# untitled.net
KiCad netlist of a schematic drawn in EAGLE
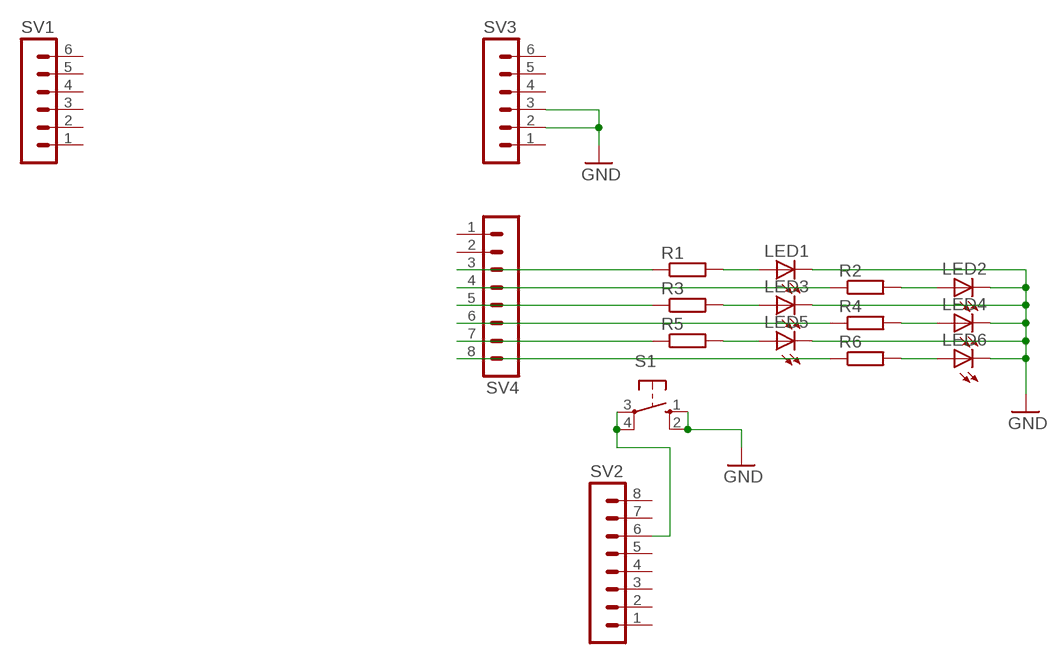
[diagram p0: schematic, sheet 1]

(export (version "E")
  (design (tool "Eeschema 10.0.6"))
  (components
    (comp (ref "LED1")
      (value "LED3MM")
      (footprint "eagle-import:LED3MM")
      (libsource (lib "eagle-import") (part "LED3MM"))
    )
    (comp (ref "LED2")
      (value "LED3MM")
      (footprint "eagle-import:LED3MM")
      (libsource (lib "eagle-import") (part "LED3MM"))
    )
    (comp (ref "LED3")
      (value "LED3MM")
      (footprint "eagle-import:LED3MM")
      (libsource (lib "eagle-import") (part "LED3MM"))
    )
    (comp (ref "LED4")
      (value "LED3MM")
      (footprint "eagle-import:LED3MM")
      (libsource (lib "eagle-import") (part "LED3MM"))
    )
    (comp (ref "LED5")
      (value "LED3MM")
      (footprint "eagle-import:LED3MM")
      (libsource (lib "eagle-import") (part "LED3MM"))
    )
    (comp (ref "LED6")
      (value "LED3MM")
      (footprint "eagle-import:LED3MM")
      (libsource (lib "eagle-import") (part "LED3MM"))
    )
    (comp (ref "R1")
      (value "R-EU_0207/10")
      (footprint "eagle-import:0207_10")
      (libsource (lib "eagle-import") (part "R-EU_0207/10"))
    )
    (comp (ref "R2")
      (value "R-EU_0207/10")
      (footprint "eagle-import:0207_10")
      (libsource (lib "eagle-import") (part "R-EU_0207/10"))
    )
    (comp (ref "R3")
      (value "R-EU_0207/10")
      (footprint "eagle-import:0207_10")
      (libsource (lib "eagle-import") (part "R-EU_0207/10"))
    )
    (comp (ref "R4")
      (value "R-EU_0207/10")
      (footprint "eagle-import:0207_10")
      (libsource (lib "eagle-import") (part "R-EU_0207/10"))
    )
    (comp (ref "R5")
      (value "R-EU_0207/10")
      (footprint "eagle-import:0207_10")
      (libsource (lib "eagle-import") (part "R-EU_0207/10"))
    )
    (comp (ref "R6")
      (value "R-EU_0207/10")
      (footprint "eagle-import:0207_10")
      (libsource (lib "eagle-import") (part "R-EU_0207/10"))
    )
    (comp (ref "S1")
      (value "40-XX")
      (footprint "eagle-import:B3F-40XX")
      (fields (field (name "MF") "OMRON COMPONENTS USA") (field (name "MPN") "B3F-4000"))
      (libsource (lib "eagle-import") (part "40-XX"))
    )
    (comp (ref "SV1")
      (value "MA06-1")
      (footprint "eagle-import:MA06-1")
      (libsource (lib "eagle-import") (part "MA06-1"))
    )
    (comp (ref "SV2")
      (value "MA08-1")
      (footprint "eagle-import:MA08-1")
      (libsource (lib "eagle-import") (part "MA08-1"))
    )
    (comp (ref "SV3")
      (value "MA06-1")
      (footprint "eagle-import:MA06-1")
      (libsource (lib "eagle-import") (part "MA06-1"))
    )
    (comp (ref "SV4")
      (value "MA08-1")
      (footprint "eagle-import:MA08-1")
      (libsource (lib "eagle-import") (part "MA08-1"))
    )
  )
  (nets
    (net (code "1") (name "GND") (class "Default")
      (node (ref "LED1") (pin "K") (pinfunction "C_K") (pintype "passive"))
      (node (ref "LED2") (pin "K") (pinfunction "C_K") (pintype "passive"))
      (node (ref "LED3") (pin "K") (pinfunction "C_K") (pintype "passive"))
      (node (ref "LED4") (pin "K") (pinfunction "C_K") (pintype "passive"))
      (node (ref "LED5") (pin "K") (pinfunction "C_K") (pintype "passive"))
      (node (ref "LED6") (pin "K") (pinfunction "C_K") (pintype "passive"))
      (node (ref "S1") (pin "1") (pinfunction "S_1") (pintype "passive"))
      (node (ref "S1") (pin "2") (pinfunction "S1_2") (pintype "passive"))
      (node (ref "SV3") (pin "2") (pinfunction "2_2") (pintype "passive"))
      (node (ref "SV3") (pin "3") (pinfunction "3_3") (pintype "passive"))
    )
    (net (code "2") (name "Net-(LED1-PadA)") (class "Default")
      (node (ref "LED1") (pin "A") (pinfunction "A_A") (pintype "passive"))
      (node (ref "R1") (pin "2") (pinfunction "2_2") (pintype "passive"))
    )
    (net (code "3") (name "Net-(LED2-PadA)") (class "Default")
      (node (ref "LED2") (pin "A") (pinfunction "A_A") (pintype "passive"))
      (node (ref "R2") (pin "2") (pinfunction "2_2") (pintype "passive"))
    )
    (net (code "4") (name "Net-(LED3-PadA)") (class "Default")
      (node (ref "LED3") (pin "A") (pinfunction "A_A") (pintype "passive"))
      (node (ref "R3") (pin "2") (pinfunction "2_2") (pintype "passive"))
    )
    (net (code "5") (name "Net-(LED4-PadA)") (class "Default")
      (node (ref "LED4") (pin "A") (pinfunction "A_A") (pintype "passive"))
      (node (ref "R4") (pin "2") (pinfunction "2_2") (pintype "passive"))
    )
    (net (code "6") (name "Net-(LED5-PadA)") (class "Default")
      (node (ref "LED5") (pin "A") (pinfunction "A_A") (pintype "passive"))
      (node (ref "R5") (pin "2") (pinfunction "2_2") (pintype "passive"))
    )
    (net (code "7") (name "Net-(LED6-PadA)") (class "Default")
      (node (ref "LED6") (pin "A") (pinfunction "A_A") (pintype "passive"))
      (node (ref "R6") (pin "2") (pinfunction "2_2") (pintype "passive"))
    )
    (net (code "8") (name "Net-(R1-Pad1)") (class "Default")
      (node (ref "R1") (pin "1") (pinfunction "1_1") (pintype "passive"))
      (node (ref "SV4") (pin "3") (pinfunction "3_3") (pintype "passive"))
    )
    (net (code "9") (name "Net-(R2-Pad1)") (class "Default")
      (node (ref "R2") (pin "1") (pinfunction "1_1") (pintype "passive"))
      (node (ref "SV4") (pin "4") (pinfunction "4_4") (pintype "passive"))
    )
    (net (code "10") (name "Net-(R3-Pad1)") (class "Default")
      (node (ref "R3") (pin "1") (pinfunction "1_1") (pintype "passive"))
      (node (ref "SV4") (pin "5") (pinfunction "5_5") (pintype "passive"))
    )
    (net (code "11") (name "Net-(R4-Pad1)") (class "Default")
      (node (ref "R4") (pin "1") (pinfunction "1_1") (pintype "passive"))
      (node (ref "SV4") (pin "6") (pinfunction "6_6") (pintype "passive"))
    )
    (net (code "12") (name "Net-(R5-Pad1)") (class "Default")
      (node (ref "R5") (pin "1") (pinfunction "1_1") (pintype "passive"))
      (node (ref "SV4") (pin "7") (pinfunction "7_7") (pintype "passive"))
    )
    (net (code "13") (name "Net-(R6-Pad1)") (class "Default")
      (node (ref "R6") (pin "1") (pinfunction "1_1") (pintype "passive"))
      (node (ref "SV4") (pin "8") (pinfunction "8_8") (pintype "passive"))
    )
    (net (code "14") (name "Net-(S1-P)") (class "Default")
      (node (ref "S1") (pin "3") (pinfunction "P_3") (pintype "passive"))
      (node (ref "S1") (pin "4") (pinfunction "P1_4") (pintype "passive"))
      (node (ref "SV2") (pin "6") (pinfunction "6_6") (pintype "passive"))
    )
    (net (code "15") (name "unconnected-(SV1-Pad1)") (class "Default")
      (node (ref "SV1") (pin "1") (pinfunction "1_1") (pintype "passive"))
    )
    (net (code "16") (name "unconnected-(SV1-Pad2)") (class "Default")
      (node (ref "SV1") (pin "2") (pinfunction "2_2") (pintype "passive"))
    )
    (net (code "17") (name "unconnected-(SV1-Pad3)") (class "Default")
      (node (ref "SV1") (pin "3") (pinfunction "3_3") (pintype "passive"))
    )
    (net (code "18") (name "unconnected-(SV1-Pad4)") (class "Default")
      (node (ref "SV1") (pin "4") (pinfunction "4_4") (pintype "passive"))
    )
    (net (code "19") (name "unconnected-(SV1-Pad5)") (class "Default")
      (node (ref "SV1") (pin "5") (pinfunction "5_5") (pintype "passive"))
    )
    (net (code "20") (name "unconnected-(SV1-Pad6)") (class "Default")
      (node (ref "SV1") (pin "6") (pinfunction "6_6") (pintype "passive"))
    )
    (net (code "21") (name "unconnected-(SV2-Pad1)") (class "Default")
      (node (ref "SV2") (pin "1") (pinfunction "1_1") (pintype "passive"))
    )
    (net (code "22") (name "unconnected-(SV2-Pad2)") (class "Default")
      (node (ref "SV2") (pin "2") (pinfunction "2_2") (pintype "passive"))
    )
    (net (code "23") (name "unconnected-(SV2-Pad3)") (class "Default")
      (node (ref "SV2") (pin "3") (pinfunction "3_3") (pintype "passive"))
    )
    (net (code "24") (name "unconnected-(SV2-Pad4)") (class "Default")
      (node (ref "SV2") (pin "4") (pinfunction "4_4") (pintype "passive"))
    )
    (net (code "25") (name "unconnected-(SV2-Pad5)") (class "Default")
      (node (ref "SV2") (pin "5") (pinfunction "5_5") (pintype "passive"))
    )
    (net (code "26") (name "unconnected-(SV2-Pad7)") (class "Default")
      (node (ref "SV2") (pin "7") (pinfunction "7_7") (pintype "passive"))
    )
    (net (code "27") (name "unconnected-(SV2-Pad8)") (class "Default")
      (node (ref "SV2") (pin "8") (pinfunction "8_8") (pintype "passive"))
    )
    (net (code "28") (name "unconnected-(SV3-Pad1)") (class "Default")
      (node (ref "SV3") (pin "1") (pinfunction "1_1") (pintype "passive"))
    )
    (net (code "29") (name "unconnected-(SV3-Pad4)") (class "Default")
      (node (ref "SV3") (pin "4") (pinfunction "4_4") (pintype "passive"))
    )
    (net (code "30") (name "unconnected-(SV3-Pad5)") (class "Default")
      (node (ref "SV3") (pin "5") (pinfunction "5_5") (pintype "passive"))
    )
    (net (code "31") (name "unconnected-(SV3-Pad6)") (class "Default")
      (node (ref "SV3") (pin "6") (pinfunction "6_6") (pintype "passive"))
    )
    (net (code "32") (name "unconnected-(SV4-Pad1)") (class "Default")
      (node (ref "SV4") (pin "1") (pinfunction "1_1") (pintype "passive"))
    )
    (net (code "33") (name "unconnected-(SV4-Pad2)") (class "Default")
      (node (ref "SV4") (pin "2") (pinfunction "2_2") (pintype "passive"))
    )
  )
)
